# freesoc_mini_1_0.net
KiCad netlist of a schematic drawn in EAGLE
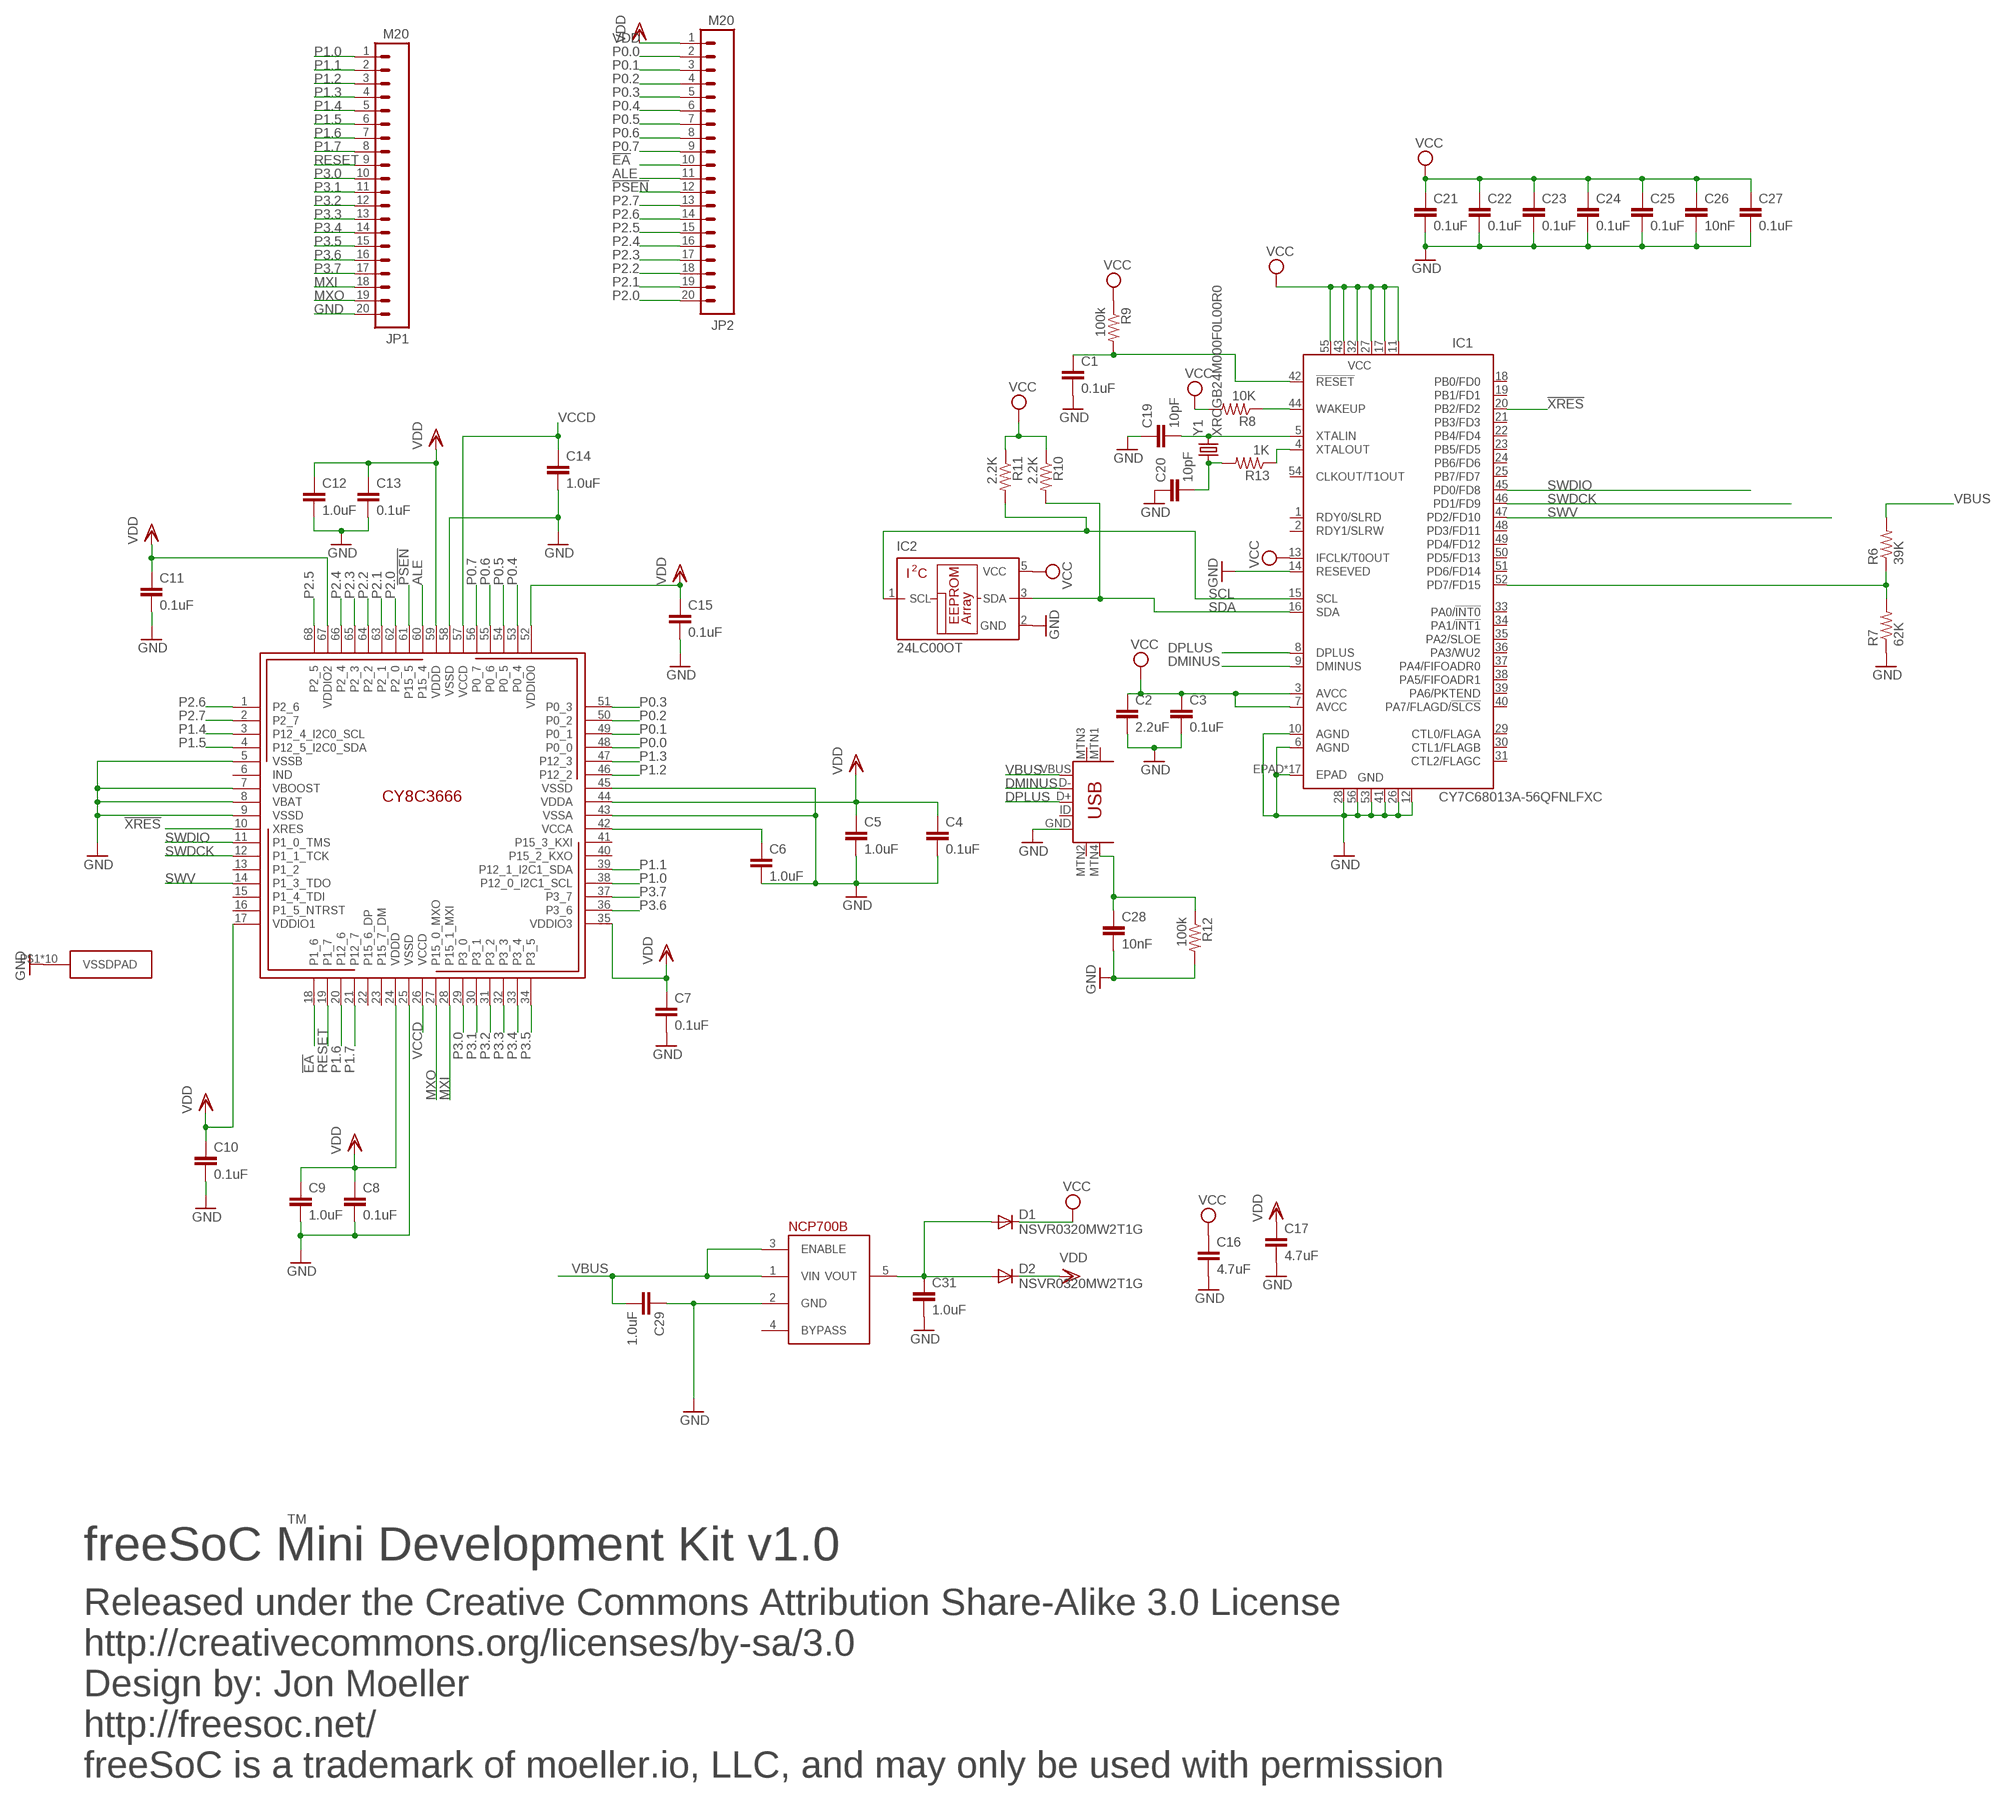
[diagram p0: schematic, sheet 1]

(export (version "E")
  (design (tool "Eeschema 10.0.6"))
  (components
    (comp (ref "C1")
      (value "0.1uF")
      (footprint "eagle-import:0402-CAP")
      (libsource (lib "eagle-import") (part "CAP0402-CAP"))
    )
    (comp (ref "C2")
      (value "2.2uF")
      (footprint "eagle-import:0402-CAP")
      (libsource (lib "eagle-import") (part "CAP0402-CAP"))
    )
    (comp (ref "C3")
      (value "0.1uF")
      (footprint "eagle-import:0402-CAP")
      (libsource (lib "eagle-import") (part "CAP0402-CAP"))
    )
    (comp (ref "C4")
      (value "0.1uF")
      (footprint "eagle-import:0402-CAP")
      (libsource (lib "eagle-import") (part "CAP0402-CAP"))
    )
    (comp (ref "C5")
      (value "1.0uF")
      (footprint "eagle-import:0402-CAP")
      (libsource (lib "eagle-import") (part "CAP0402-CAP"))
    )
    (comp (ref "C6")
      (value "1.0uF")
      (footprint "eagle-import:0402-CAP")
      (libsource (lib "eagle-import") (part "CAP0402-CAP"))
    )
    (comp (ref "C7")
      (value "0.1uF")
      (footprint "eagle-import:0402-CAP")
      (libsource (lib "eagle-import") (part "CAP0402-CAP"))
    )
    (comp (ref "C8")
      (value "0.1uF")
      (footprint "eagle-import:0402-CAP")
      (libsource (lib "eagle-import") (part "CAP0402-CAP"))
    )
    (comp (ref "C9")
      (value "1.0uF")
      (footprint "eagle-import:0402-CAP")
      (libsource (lib "eagle-import") (part "CAP0402-CAP"))
    )
    (comp (ref "C10")
      (value "0.1uF")
      (footprint "eagle-import:0402-CAP")
      (libsource (lib "eagle-import") (part "CAP0402-CAP"))
    )
    (comp (ref "C11")
      (value "0.1uF")
      (footprint "eagle-import:0402-CAP")
      (libsource (lib "eagle-import") (part "CAP0402-CAP"))
    )
    (comp (ref "C12")
      (value "1.0uF")
      (footprint "eagle-import:0402-CAP")
      (libsource (lib "eagle-import") (part "CAP0402-CAP"))
    )
    (comp (ref "C13")
      (value "0.1uF")
      (footprint "eagle-import:0402-CAP")
      (libsource (lib "eagle-import") (part "CAP0402-CAP"))
    )
    (comp (ref "C14")
      (value "1.0uF")
      (footprint "eagle-import:0402-CAP")
      (libsource (lib "eagle-import") (part "CAP0402-CAP"))
    )
    (comp (ref "C15")
      (value "0.1uF")
      (footprint "eagle-import:0402-CAP")
      (libsource (lib "eagle-import") (part "CAP0402-CAP"))
    )
    (comp (ref "C16")
      (value "4.7uF")
      (footprint "eagle-import:0603-CAP")
      (libsource (lib "eagle-import") (part "CAP0603-CAP"))
    )
    (comp (ref "C17")
      (value "4.7uF")
      (footprint "eagle-import:0603-CAP")
      (libsource (lib "eagle-import") (part "CAP0603-CAP"))
    )
    (comp (ref "C19")
      (value "10pF")
      (footprint "eagle-import:0402-CAP")
      (libsource (lib "eagle-import") (part "CAP0402-CAP"))
    )
    (comp (ref "C20")
      (value "10pF")
      (footprint "eagle-import:0402-CAP")
      (libsource (lib "eagle-import") (part "CAP0402-CAP"))
    )
    (comp (ref "C21")
      (value "0.1uF")
      (footprint "eagle-import:0402-CAP")
      (libsource (lib "eagle-import") (part "CAP0402-CAP"))
    )
    (comp (ref "C22")
      (value "0.1uF")
      (footprint "eagle-import:0402-CAP")
      (libsource (lib "eagle-import") (part "CAP0402-CAP"))
    )
    (comp (ref "C23")
      (value "0.1uF")
      (footprint "eagle-import:0402-CAP")
      (libsource (lib "eagle-import") (part "CAP0402-CAP"))
    )
    (comp (ref "C24")
      (value "0.1uF")
      (footprint "eagle-import:0402-CAP")
      (libsource (lib "eagle-import") (part "CAP0402-CAP"))
    )
    (comp (ref "C25")
      (value "0.1uF")
      (footprint "eagle-import:0402-CAP")
      (libsource (lib "eagle-import") (part "CAP0402-CAP"))
    )
    (comp (ref "C26")
      (value "10nF")
      (footprint "eagle-import:0402-CAP")
      (libsource (lib "eagle-import") (part "CAP0402-CAP"))
    )
    (comp (ref "C27")
      (value "0.1uF")
      (footprint "eagle-import:0402-CAP")
      (libsource (lib "eagle-import") (part "CAP0402-CAP"))
    )
    (comp (ref "C28")
      (value "10nF")
      (footprint "eagle-import:0402-CAP")
      (libsource (lib "eagle-import") (part "CAP0402-CAP"))
    )
    (comp (ref "C29")
      (value "1.0uF")
      (footprint "eagle-import:0402-CAP")
      (libsource (lib "eagle-import") (part "CAP0402-CAP"))
    )
    (comp (ref "C31")
      (value "1.0uF")
      (footprint "eagle-import:0402-CAP")
      (libsource (lib "eagle-import") (part "CAP0402-CAP"))
    )
    (comp (ref "D1")
      (value "NSVR0320MW2T1G")
      (footprint "eagle-import:SOD-323")
      (libsource (lib "eagle-import") (part "DIODESOD"))
    )
    (comp (ref "D2")
      (value "NSVR0320MW2T1G")
      (footprint "eagle-import:SOD-323")
      (libsource (lib "eagle-import") (part "DIODESOD"))
    )
    (comp (ref "IC1")
      (value "CY7C68013A-56QFNLFXC")
      (footprint "eagle-import:QFN56")
      (libsource (lib "eagle-import") (part "CY7C6801A-56QFNLFXC3"))
    )
    (comp (ref "IC2")
      (value "24LC00OT")
      (footprint "eagle-import:SOT23-5L")
      (libsource (lib "eagle-import") (part "2400OTLC"))
    )
    (comp (ref "JP1")
      (value "M20")
      (footprint "eagle-import:1X20")
      (libsource (lib "eagle-import") (part "M20"))
    )
    (comp (ref "JP2")
      (value "M20")
      (footprint "eagle-import:1X20")
      (libsource (lib "eagle-import") (part "M20"))
    )
    (comp (ref "R6")
      (value "39K")
      (footprint "eagle-import:0402-RES")
      (libsource (lib "eagle-import") (part "RESISTOR0402-RES"))
    )
    (comp (ref "R7")
      (value "62K")
      (footprint "eagle-import:0402-RES")
      (libsource (lib "eagle-import") (part "RESISTOR0402-RES"))
    )
    (comp (ref "R8")
      (value "10K")
      (footprint "eagle-import:0402-RES")
      (libsource (lib "eagle-import") (part "RESISTOR0402-RES"))
    )
    (comp (ref "R9")
      (value "100k")
      (footprint "eagle-import:0402-RES")
      (libsource (lib "eagle-import") (part "RESISTOR0402-RES"))
    )
    (comp (ref "R10")
      (value "2.2K")
      (footprint "eagle-import:0402-RES")
      (libsource (lib "eagle-import") (part "RESISTOR0402-RES"))
    )
    (comp (ref "R11")
      (value "2.2K")
      (footprint "eagle-import:0402-RES")
      (libsource (lib "eagle-import") (part "RESISTOR0402-RES"))
    )
    (comp (ref "R12")
      (value "100k")
      (footprint "eagle-import:0402-RES")
      (libsource (lib "eagle-import") (part "RESISTOR0402-RES"))
    )
    (comp (ref "R13")
      (value "1K")
      (footprint "eagle-import:0402-RES")
      (libsource (lib "eagle-import") (part "RESISTOR0402-RES"))
    )
    (comp (ref "U$1")
      (value "CY8C3X66LTI")
      (footprint "eagle-import:QFN-68")
      (fields (field (name "PN") "CY8C5568LTI-114"))
      (libsource (lib "eagle-import") (part "CY8C3X66LTI"))
    )
    (comp (ref "U$3")
      (value "FAN2558S36X")
      (footprint "eagle-import:TSOP-5")
      (libsource (lib "eagle-import") (part "NCP700B"))
    )
    (comp (ref "USB-MINIB")
      (value "USB-MINIB-5PIN")
      (footprint "eagle-import:USB-MINIB")
      (libsource (lib "eagle-import") (part "USB-MINIB-5PIN"))
    )
    (comp (ref "Y1")
      (value "XRCGB24M000F0L00R0")
      (footprint "eagle-import:CRYSTAL_RESONATOR")
      (libsource (lib "eagle-import") (part "CRYSTALXRCGB"))
    )
  )
  (nets
    (net (code "1") (name "/ALE") (class "Default")
      (node (ref "JP2") (pin "11") (pinfunction "11_11") (pintype "passive"))
      (node (ref "U$1") (pin "60") (pinfunction "P15_4_60") (pintype "passive"))
    )
    (net (code "2") (name "/DMINUS") (class "Default")
      (node (ref "IC1") (pin "9") (pinfunction "DMINUS_9") (pintype "bidirectional"))
      (node (ref "USB-MINIB") (pin "D-") (pinfunction "D-_D-") (pintype "bidirectional"))
    )
    (net (code "3") (name "/DPLUS") (class "Default")
      (node (ref "IC1") (pin "8") (pinfunction "DPLUS_8") (pintype "bidirectional"))
      (node (ref "USB-MINIB") (pin "D+") (pinfunction "D+_D+") (pintype "bidirectional"))
    )
    (net (code "4") (name "/MXI") (class "Default")
      (node (ref "JP1") (pin "18") (pinfunction "18_18") (pintype "passive"))
      (node (ref "U$1") (pin "28") (pinfunction "P15_1_MXI_28") (pintype "passive"))
    )
    (net (code "5") (name "/MXO") (class "Default")
      (node (ref "JP1") (pin "19") (pinfunction "19_19") (pintype "passive"))
      (node (ref "U$1") (pin "27") (pinfunction "P15_0_MXO_27") (pintype "passive"))
    )
    (net (code "6") (name "/P0.0") (class "Default")
      (node (ref "JP2") (pin "2") (pinfunction "2_2") (pintype "passive"))
      (node (ref "U$1") (pin "48") (pinfunction "P0_0_48") (pintype "passive"))
    )
    (net (code "7") (name "/P0.1") (class "Default")
      (node (ref "JP2") (pin "3") (pinfunction "3_3") (pintype "passive"))
      (node (ref "U$1") (pin "49") (pinfunction "P0_1_49") (pintype "passive"))
    )
    (net (code "8") (name "/P0.2") (class "Default")
      (node (ref "JP2") (pin "4") (pinfunction "4_4") (pintype "passive"))
      (node (ref "U$1") (pin "50") (pinfunction "P0_2_50") (pintype "passive"))
    )
    (net (code "9") (name "/P0.3") (class "Default")
      (node (ref "JP2") (pin "5") (pinfunction "5_5") (pintype "passive"))
      (node (ref "U$1") (pin "51") (pinfunction "P0_3_51") (pintype "passive"))
    )
    (net (code "10") (name "/P0.4") (class "Default")
      (node (ref "JP2") (pin "6") (pinfunction "6_6") (pintype "passive"))
      (node (ref "U$1") (pin "53") (pinfunction "P0_4_53") (pintype "passive"))
    )
    (net (code "11") (name "/P0.5") (class "Default")
      (node (ref "JP2") (pin "7") (pinfunction "7_7") (pintype "passive"))
      (node (ref "U$1") (pin "54") (pinfunction "P0_5_54") (pintype "passive"))
    )
    (net (code "12") (name "/P0.6") (class "Default")
      (node (ref "JP2") (pin "8") (pinfunction "8_8") (pintype "passive"))
      (node (ref "U$1") (pin "55") (pinfunction "P0_6_55") (pintype "passive"))
    )
    (net (code "13") (name "/P0.7") (class "Default")
      (node (ref "JP2") (pin "9") (pinfunction "9_9") (pintype "passive"))
      (node (ref "U$1") (pin "56") (pinfunction "P0_7_56") (pintype "passive"))
    )
    (net (code "14") (name "/P1.0") (class "Default")
      (node (ref "JP1") (pin "1") (pinfunction "1_1") (pintype "passive"))
      (node (ref "U$1") (pin "38") (pinfunction "P12_0_I2C1_SCL_38") (pintype "passive"))
    )
    (net (code "15") (name "/P1.1") (class "Default")
      (node (ref "JP1") (pin "2") (pinfunction "2_2") (pintype "passive"))
      (node (ref "U$1") (pin "39") (pinfunction "P12_1_I2C1_SDA_39") (pintype "passive"))
    )
    (net (code "16") (name "/P1.2") (class "Default")
      (node (ref "JP1") (pin "3") (pinfunction "3_3") (pintype "passive"))
      (node (ref "U$1") (pin "46") (pinfunction "P12_2_46") (pintype "passive"))
    )
    (net (code "17") (name "/P1.3") (class "Default")
      (node (ref "JP1") (pin "4") (pinfunction "4_4") (pintype "passive"))
      (node (ref "U$1") (pin "47") (pinfunction "P12_3_47") (pintype "passive"))
    )
    (net (code "18") (name "/P1.4") (class "Default")
      (node (ref "JP1") (pin "5") (pinfunction "5_5") (pintype "passive"))
      (node (ref "U$1") (pin "3") (pinfunction "P12_4_I2C0_SCL_3") (pintype "passive"))
    )
    (net (code "19") (name "/P1.5") (class "Default")
      (node (ref "JP1") (pin "6") (pinfunction "6_6") (pintype "passive"))
      (node (ref "U$1") (pin "4") (pinfunction "P12_5_I2C0_SDA_4") (pintype "passive"))
    )
    (net (code "20") (name "/P1.6") (class "Default")
      (node (ref "JP1") (pin "7") (pinfunction "7_7") (pintype "passive"))
      (node (ref "U$1") (pin "20") (pinfunction "P12_6_20") (pintype "passive"))
    )
    (net (code "21") (name "/P1.7") (class "Default")
      (node (ref "JP1") (pin "8") (pinfunction "8_8") (pintype "passive"))
      (node (ref "U$1") (pin "21") (pinfunction "P12_7_21") (pintype "passive"))
    )
    (net (code "22") (name "/P2.0") (class "Default")
      (node (ref "JP2") (pin "20") (pinfunction "20_20") (pintype "passive"))
      (node (ref "U$1") (pin "62") (pinfunction "P2_0_62") (pintype "passive"))
    )
    (net (code "23") (name "/P2.1") (class "Default")
      (node (ref "JP2") (pin "19") (pinfunction "19_19") (pintype "passive"))
      (node (ref "U$1") (pin "63") (pinfunction "P2_1_63") (pintype "passive"))
    )
    (net (code "24") (name "/P2.2") (class "Default")
      (node (ref "JP2") (pin "18") (pinfunction "18_18") (pintype "passive"))
      (node (ref "U$1") (pin "64") (pinfunction "P2_2_64") (pintype "passive"))
    )
    (net (code "25") (name "/P2.3") (class "Default")
      (node (ref "JP2") (pin "17") (pinfunction "17_17") (pintype "passive"))
      (node (ref "U$1") (pin "65") (pinfunction "P2_3_65") (pintype "passive"))
    )
    (net (code "26") (name "/P2.4") (class "Default")
      (node (ref "JP2") (pin "16") (pinfunction "16_16") (pintype "passive"))
      (node (ref "U$1") (pin "66") (pinfunction "P2_4_66") (pintype "passive"))
    )
    (net (code "27") (name "/P2.5") (class "Default")
      (node (ref "JP2") (pin "15") (pinfunction "15_15") (pintype "passive"))
      (node (ref "U$1") (pin "68") (pinfunction "P2_5_68") (pintype "passive"))
    )
    (net (code "28") (name "/P2.6") (class "Default")
      (node (ref "JP2") (pin "14") (pinfunction "14_14") (pintype "passive"))
      (node (ref "U$1") (pin "1") (pinfunction "P2_6_1") (pintype "passive"))
    )
    (net (code "29") (name "/P2.7") (class "Default")
      (node (ref "JP2") (pin "13") (pinfunction "13_13") (pintype "passive"))
      (node (ref "U$1") (pin "2") (pinfunction "P2_7_2") (pintype "passive"))
    )
    (net (code "30") (name "/P3.0") (class "Default")
      (node (ref "JP1") (pin "10") (pinfunction "10_10") (pintype "passive"))
      (node (ref "U$1") (pin "29") (pinfunction "P3_0_29") (pintype "passive"))
    )
    (net (code "31") (name "/P3.1") (class "Default")
      (node (ref "JP1") (pin "11") (pinfunction "11_11") (pintype "passive"))
      (node (ref "U$1") (pin "30") (pinfunction "P3_1_30") (pintype "passive"))
    )
    (net (code "32") (name "/P3.2") (class "Default")
      (node (ref "JP1") (pin "12") (pinfunction "12_12") (pintype "passive"))
      (node (ref "U$1") (pin "31") (pinfunction "P3_2_31") (pintype "passive"))
    )
    (net (code "33") (name "/P3.3") (class "Default")
      (node (ref "JP1") (pin "13") (pinfunction "13_13") (pintype "passive"))
      (node (ref "U$1") (pin "32") (pinfunction "P3_3_32") (pintype "passive"))
    )
    (net (code "34") (name "/P3.4") (class "Default")
      (node (ref "JP1") (pin "14") (pinfunction "14_14") (pintype "passive"))
      (node (ref "U$1") (pin "33") (pinfunction "P3_4_33") (pintype "passive"))
    )
    (net (code "35") (name "/P3.5") (class "Default")
      (node (ref "JP1") (pin "15") (pinfunction "15_15") (pintype "passive"))
      (node (ref "U$1") (pin "34") (pinfunction "P3_5_34") (pintype "passive"))
    )
    (net (code "36") (name "/P3.6") (class "Default")
      (node (ref "JP1") (pin "16") (pinfunction "16_16") (pintype "passive"))
      (node (ref "U$1") (pin "36") (pinfunction "P3_6_36") (pintype "passive"))
    )
    (net (code "37") (name "/P3.7") (class "Default")
      (node (ref "JP1") (pin "17") (pinfunction "17_17") (pintype "passive"))
      (node (ref "U$1") (pin "37") (pinfunction "P3_7_37") (pintype "passive"))
    )
    (net (code "38") (name "/RESET") (class "Default")
      (node (ref "JP1") (pin "9") (pinfunction "9_9") (pintype "passive"))
      (node (ref "U$1") (pin "19") (pinfunction "P1_7_19") (pintype "passive"))
    )
    (net (code "39") (name "/SCL") (class "Default")
      (node (ref "IC1") (pin "15") (pinfunction "SCL_15") (pintype "output"))
      (node (ref "IC2") (pin "1") (pinfunction "SCL_1") (pintype "input"))
      (node (ref "R11") (pin "2") (pinfunction "2_2") (pintype "passive"))
    )
    (net (code "40") (name "/SDA") (class "Default")
      (node (ref "IC1") (pin "16") (pinfunction "SDA_16") (pintype "bidirectional"))
      (node (ref "IC2") (pin "3") (pinfunction "SDA_3") (pintype "bidirectional"))
      (node (ref "R10") (pin "2") (pinfunction "2_2") (pintype "passive"))
    )
    (net (code "41") (name "/SWDCK") (class "Default")
      (node (ref "IC1") (pin "46") (pinfunction "PD1/FD9_46") (pintype "bidirectional"))
      (node (ref "U$1") (pin "12") (pinfunction "P1_1_TCK_12") (pintype "passive"))
    )
    (net (code "42") (name "/SWDIO") (class "Default")
      (node (ref "IC1") (pin "45") (pinfunction "PD0/FD8_45") (pintype "bidirectional"))
      (node (ref "U$1") (pin "11") (pinfunction "P1_0_TMS_11") (pintype "passive"))
    )
    (net (code "43") (name "/SWV") (class "Default")
      (node (ref "IC1") (pin "47") (pinfunction "PD2/FD10_47") (pintype "bidirectional"))
      (node (ref "U$1") (pin "14") (pinfunction "P1_3_TDO_14") (pintype "passive"))
    )
    (net (code "44") (name "/VBUS") (class "Default")
      (node (ref "C29") (pin "2") (pinfunction "2_2") (pintype "passive"))
      (node (ref "R6") (pin "2") (pinfunction "2_2") (pintype "passive"))
      (node (ref "U$3") (pin "1") (pinfunction "VIN_1") (pintype "bidirectional"))
      (node (ref "U$3") (pin "3") (pinfunction "ENABLE_3") (pintype "bidirectional"))
      (node (ref "USB-MINIB") (pin "VBUS") (pinfunction "VBUS_VBUS") (pintype "bidirectional"))
    )
    (net (code "45") (name "/VCCD") (class "Default")
      (node (ref "C14") (pin "1") (pinfunction "1_1") (pintype "passive"))
      (node (ref "U$1") (pin "26") (pinfunction "VCCD_26") (pintype "passive"))
      (node (ref "U$1") (pin "57") (pinfunction "VCCD_57") (pintype "passive"))
    )
    (net (code "46") (name "/~{EA}") (class "Default")
      (node (ref "JP2") (pin "10") (pinfunction "10_10") (pintype "passive"))
      (node (ref "U$1") (pin "18") (pinfunction "P1_6_18") (pintype "passive"))
    )
    (net (code "47") (name "/~{PSEN}") (class "Default")
      (node (ref "JP2") (pin "12") (pinfunction "12_12") (pintype "passive"))
      (node (ref "U$1") (pin "61") (pinfunction "P15_5_61") (pintype "passive"))
    )
    (net (code "48") (name "/~{XRES}") (class "Default")
      (node (ref "IC1") (pin "20") (pinfunction "PB2/FD2_20") (pintype "bidirectional"))
      (node (ref "U$1") (pin "10") (pinfunction "XRES_10") (pintype "passive"))
    )
    (net (code "49") (name "GND") (class "Default")
      (node (ref "C1") (pin "2") (pinfunction "2_2") (pintype "passive"))
      (node (ref "C10") (pin "2") (pinfunction "2_2") (pintype "passive"))
      (node (ref "C11") (pin "2") (pinfunction "2_2") (pintype "passive"))
      (node (ref "C12") (pin "2") (pinfunction "2_2") (pintype "passive"))
      (node (ref "C13") (pin "2") (pinfunction "2_2") (pintype "passive"))
      (node (ref "C14") (pin "2") (pinfunction "2_2") (pintype "passive"))
      (node (ref "C15") (pin "2") (pinfunction "2_2") (pintype "passive"))
      (node (ref "C16") (pin "2") (pinfunction "2_2") (pintype "passive"))
      (node (ref "C17") (pin "2") (pinfunction "2_2") (pintype "passive"))
      (node (ref "C19") (pin "1") (pinfunction "1_1") (pintype "passive"))
      (node (ref "C2") (pin "2") (pinfunction "2_2") (pintype "passive"))
      (node (ref "C20") (pin "1") (pinfunction "1_1") (pintype "passive"))
      (node (ref "C21") (pin "2") (pinfunction "2_2") (pintype "passive"))
      (node (ref "C22") (pin "2") (pinfunction "2_2") (pintype "passive"))
      (node (ref "C23") (pin "2") (pinfunction "2_2") (pintype "passive"))
      (node (ref "C24") (pin "2") (pinfunction "2_2") (pintype "passive"))
      (node (ref "C25") (pin "2") (pinfunction "2_2") (pintype "passive"))
      (node (ref "C26") (pin "2") (pinfunction "2_2") (pintype "passive"))
      (node (ref "C27") (pin "2") (pinfunction "2_2") (pintype "passive"))
      (node (ref "C28") (pin "2") (pinfunction "2_2") (pintype "passive"))
      (node (ref "C29") (pin "1") (pinfunction "1_1") (pintype "passive"))
      (node (ref "C3") (pin "2") (pinfunction "2_2") (pintype "passive"))
      (node (ref "C31") (pin "2") (pinfunction "2_2") (pintype "passive"))
      (node (ref "C4") (pin "2") (pinfunction "2_2") (pintype "passive"))
      (node (ref "C5") (pin "2") (pinfunction "2_2") (pintype "passive"))
      (node (ref "C6") (pin "2") (pinfunction "2_2") (pintype "passive"))
      (node (ref "C7") (pin "2") (pinfunction "2_2") (pintype "passive"))
      (node (ref "C8") (pin "2") (pinfunction "2_2") (pintype "passive"))
      (node (ref "C9") (pin "2") (pinfunction "2_2") (pintype "passive"))
      (node (ref "IC1") (pin "10") (pinfunction "AGND_10") (pintype "input"))
      (node (ref "IC1") (pin "12") (pinfunction "GND_12") (pintype "input"))
      (node (ref "IC1") (pin "14") (pinfunction "RESEVED_14") (pintype "input"))
      (node (ref "IC1") (pin "26") (pinfunction "GND_26") (pintype "input"))
      (node (ref "IC1") (pin "28") (pinfunction "GND_28") (pintype "input"))
      (node (ref "IC1") (pin "41") (pinfunction "GND_41") (pintype "input"))
      (node (ref "IC1") (pin "53") (pinfunction "GND_53") (pintype "input"))
      (node (ref "IC1") (pin "56") (pinfunction "GND_56") (pintype "input"))
      (node (ref "IC1") (pin "6") (pinfunction "AGND_6") (pintype "input"))
      (node (ref "IC1") (pin "EPAD") (pinfunction "EPAD_EPAD") (pintype "passive"))
      (node (ref "IC1") (pin "P$1") (pinfunction "EPAD_P$1") (pintype "passive"))
      (node (ref "IC1") (pin "P$10") (pinfunction "EPAD_P$10") (pintype "passive"))
      (node (ref "IC1") (pin "P$11") (pinfunction "EPAD_P$11") (pintype "passive"))
      (node (ref "IC1") (pin "P$12") (pinfunction "EPAD_P$12") (pintype "passive"))
      (node (ref "IC1") (pin "P$13") (pinfunction "EPAD_P$13") (pintype "passive"))
      (node (ref "IC1") (pin "P$14") (pinfunction "EPAD_P$14") (pintype "passive"))
      (node (ref "IC1") (pin "P$15") (pinfunction "EPAD_P$15") (pintype "passive"))
      (node (ref "IC1") (pin "P$16") (pinfunction "EPAD_P$16") (pintype "passive"))
      (node (ref "IC1") (pin "P$2") (pinfunction "EPAD_P$2") (pintype "passive"))
      (node (ref "IC1") (pin "P$3") (pinfunction "EPAD_P$3") (pintype "passive"))
      (node (ref "IC1") (pin "P$4") (pinfunction "EPAD_P$4") (pintype "passive"))
      (node (ref "IC1") (pin "P$5") (pinfunction "EPAD_P$5") (pintype "passive"))
      (node (ref "IC1") (pin "P$6") (pinfunction "EPAD_P$6") (pintype "passive"))
      (node (ref "IC1") (pin "P$7") (pinfunction "EPAD_P$7") (pintype "passive"))
      (node (ref "IC1") (pin "P$8") (pinfunction "EPAD_P$8") (pintype "passive"))
      (node (ref "IC1") (pin "P$9") (pinfunction "EPAD_P$9") (pintype "passive"))
      (node (ref "IC2") (pin "2") (pinfunction "GND_2") (pintype "power_in"))
      (node (ref "JP1") (pin "20") (pinfunction "20_20") (pintype "passive"))
      (node (ref "R12") (pin "2") (pinfunction "2_2") (pintype "passive"))
      (node (ref "R7") (pin "1") (pinfunction "1_1") (pintype "passive"))
      (node (ref "U$1") (pin "25") (pinfunction "VSSD_25") (pintype "passive"))
      (node (ref "U$1") (pin "43") (pinfunction "VSSA_43") (pintype "passive"))
      (node (ref "U$1") (pin "45") (pinfunction "VSSD_45") (pintype "passive"))
      (node (ref "U$1") (pin "5") (pinfunction "VSSB_5") (pintype "passive"))
      (node (ref "U$1") (pin "58") (pinfunction "VSSD_58") (pintype "passive"))
      (node (ref "U$1") (pin "7") (pinfunction "VBOOST_7") (pintype "passive"))
      (node (ref "U$1") (pin "8") (pinfunction "VBAT_8") (pintype "passive"))
      (node (ref "U$1") (pin "9") (pinfunction "VSSD_9") (pintype "passive"))
      (node (ref "U$1") (pin "P$1") (pinfunction "VSSDPAD_P$1") (pintype "power_in"))
      (node (ref "U$1") (pin "P$2") (pinfunction "VSSDPAD_P$2") (pintype "power_in"))
      (node (ref "U$1") (pin "P$3") (pinfunction "VSSDPAD_P$3") (pintype "power_in"))
      (node (ref "U$1") (pin "P$4") (pinfunction "VSSDPAD_P$4") (pintype "power_in"))
      (node (ref "U$1") (pin "P$5") (pinfunction "VSSDPAD_P$5") (pintype "power_in"))
      (node (ref "U$1") (pin "P$6") (pinfunction "VSSDPAD_P$6") (pintype "power_in"))
      (node (ref "U$1") (pin "P$7") (pinfunction "VSSDPAD_P$7") (pintype "power_in"))
      (node (ref "U$1") (pin "P$8") (pinfunction "VSSDPAD_P$8") (pintype "power_in"))
      (node (ref "U$1") (pin "P$9") (pinfunction "VSSDPAD_P$9") (pintype "power_in"))
      (node (ref "U$1") (pin "PAD") (pinfunction "VSSDPAD_PAD") (pintype "power_in"))
      (node (ref "U$3") (pin "2") (pinfunction "GND_2") (pintype "bidirectional"))
      (node (ref "USB-MINIB") (pin "GND") (pinfunction "GND_GND") (pintype "bidirectional"))
    )
    (net (code "50") (name "Net-(C28-Pad1)") (class "Default")
      (node (ref "C28") (pin "1") (pinfunction "1_1") (pintype "passive"))
      (node (ref "R12") (pin "1") (pinfunction "1_1") (pintype "passive"))
      (node (ref "USB-MINIB") (pin "MTN4") (pinfunction "MTN4_MTN4") (pintype "bidirectional"))
    )
    (net (code "51") (name "Net-(D1-A)") (class "Default")
      (node (ref "C31") (pin "1") (pinfunction "1_1") (pintype "passive"))
      (node (ref "D1") (pin "2") (pinfunction "A_2") (pintype "passive"))
      (node (ref "D2") (pin "2") (pinfunction "A_2") (pintype "passive"))
      (node (ref "U$3") (pin "5") (pinfunction "VOUT_5") (pintype "bidirectional"))
    )
    (net (code "52") (name "Net-(IC1-PD7{slash}FD15)") (class "Default")
      (node (ref "IC1") (pin "52") (pinfunction "PD7/FD15_52") (pintype "bidirectional"))
      (node (ref "R6") (pin "1") (pinfunction "1_1") (pintype "passive"))
      (node (ref "R7") (pin "2") (pinfunction "2_2") (pintype "passive"))
    )
    (net (code "53") (name "Net-(IC1-WAKEUP)") (class "Default")
      (node (ref "IC1") (pin "44") (pinfunction "WAKEUP_44") (pintype "input"))
      (node (ref "R8") (pin "1") (pinfunction "1_1") (pintype "passive"))
    )
    (net (code "54") (name "Net-(IC1-XTALIN)") (class "Default")
      (node (ref "C19") (pin "2") (pinfunction "2_2") (pintype "passive"))
      (node (ref "IC1") (pin "5") (pinfunction "XTALIN_5") (pintype "input"))
      (node (ref "Y1") (pin "P$4") (pinfunction "2_P$4") (pintype "passive"))
    )
    (net (code "55") (name "Net-(IC1-XTALOUT)") (class "Default")
      (node (ref "IC1") (pin "4") (pinfunction "XTALOUT_4") (pintype "input"))
      (node (ref "R13") (pin "1") (pinfunction "1_1") (pintype "passive"))
    )
    (net (code "56") (name "Net-(IC1-~{RESET})") (class "Default")
      (node (ref "C1") (pin "1") (pinfunction "1_1") (pintype "passive"))
      (node (ref "IC1") (pin "42") (pinfunction "~{RESET}_42") (pintype "input"))
      (node (ref "R9") (pin "2") (pinfunction "2_2") (pintype "passive"))
    )
    (net (code "57") (name "Net-(U$1A-VCCA)") (class "Default")
      (node (ref "C6") (pin "1") (pinfunction "1_1") (pintype "passive"))
      (node (ref "U$1") (pin "42") (pinfunction "VCCA_42") (pintype "passive"))
    )
    (net (code "58") (name "Net-(Y1-1)") (class "Default")
      (node (ref "C20") (pin "2") (pinfunction "2_2") (pintype "passive"))
      (node (ref "R13") (pin "2") (pinfunction "2_2") (pintype "passive"))
      (node (ref "Y1") (pin "P$1") (pinfunction "1_P$1") (pintype "passive"))
    )
    (net (code "59") (name "VCC") (class "Default")
      (node (ref "C16") (pin "1") (pinfunction "1_1") (pintype "passive"))
      (node (ref "C2") (pin "1") (pinfunction "1_1") (pintype "passive"))
      (node (ref "C21") (pin "1") (pinfunction "1_1") (pintype "passive"))
      (node (ref "C22") (pin "1") (pinfunction "1_1") (pintype "passive"))
      (node (ref "C23") (pin "1") (pinfunction "1_1") (pintype "passive"))
      (node (ref "C24") (pin "1") (pinfunction "1_1") (pintype "passive"))
      (node (ref "C25") (pin "1") (pinfunction "1_1") (pintype "passive"))
      (node (ref "C26") (pin "1") (pinfunction "1_1") (pintype "passive"))
      (node (ref "C27") (pin "1") (pinfunction "1_1") (pintype "passive"))
      (node (ref "C3") (pin "1") (pinfunction "1_1") (pintype "passive"))
      (node (ref "D1") (pin "1") (pinfunction "C_1") (pintype "passive"))
      (node (ref "IC1") (pin "11") (pinfunction "VCC_11") (pintype "input"))
      (node (ref "IC1") (pin "13") (pinfunction "IFCLK/T0OUT_13") (pintype "bidirectional"))
      (node (ref "IC1") (pin "17") (pinfunction "VCC_17") (pintype "input"))
      (node (ref "IC1") (pin "27") (pinfunction "VCC_27") (pintype "input"))
      (node (ref "IC1") (pin "3") (pinfunction "AVCC_3") (pintype "input"))
      (node (ref "IC1") (pin "32") (pinfunction "VCC_32") (pintype "input"))
      (node (ref "IC1") (pin "43") (pinfunction "VCC_43") (pintype "input"))
      (node (ref "IC1") (pin "55") (pinfunction "VCC_55") (pintype "input"))
      (node (ref "IC1") (pin "7") (pinfunction "AVCC_7") (pintype "input"))
      (node (ref "IC2") (pin "5") (pinfunction "VCC_5") (pintype "power_in"))
      (node (ref "R10") (pin "1") (pinfunction "1_1") (pintype "passive"))
      (node (ref "R11") (pin "1") (pinfunction "1_1") (pintype "passive"))
      (node (ref "R8") (pin "2") (pinfunction "2_2") (pintype "passive"))
      (node (ref "R9") (pin "1") (pinfunction "1_1") (pintype "passive"))
    )
    (net (code "60") (name "VDD") (class "Default")
      (node (ref "C10") (pin "1") (pinfunction "1_1") (pintype "passive"))
      (node (ref "C11") (pin "1") (pinfunction "1_1") (pintype "passive"))
      (node (ref "C12") (pin "1") (pinfunction "1_1") (pintype "passive"))
      (node (ref "C13") (pin "1") (pinfunction "1_1") (pintype "passive"))
      (node (ref "C15") (pin "1") (pinfunction "1_1") (pintype "passive"))
      (node (ref "C17") (pin "1") (pinfunction "1_1") (pintype "passive"))
      (node (ref "C4") (pin "1") (pinfunction "1_1") (pintype "passive"))
      (node (ref "C5") (pin "1") (pinfunction "1_1") (pintype "passive"))
      (node (ref "C7") (pin "1") (pinfunction "1_1") (pintype "passive"))
      (node (ref "C8") (pin "1") (pinfunction "1_1") (pintype "passive"))
      (node (ref "C9") (pin "1") (pinfunction "1_1") (pintype "passive"))
      (node (ref "D2") (pin "1") (pinfunction "C_1") (pintype "passive"))
      (node (ref "JP2") (pin "1") (pinfunction "1_1") (pintype "passive"))
      (node (ref "U$1") (pin "17") (pinfunction "VDDIO1_17") (pintype "passive"))
      (node (ref "U$1") (pin "24") (pinfunction "VDDD_24") (pintype "passive"))
      (node (ref "U$1") (pin "35") (pinfunction "VDDIO3_35") (pintype "passive"))
      (node (ref "U$1") (pin "44") (pinfunction "VDDA_44") (pintype "passive"))
      (node (ref "U$1") (pin "52") (pinfunction "VDDIO0_52") (pintype "passive"))
      (node (ref "U$1") (pin "59") (pinfunction "VDDD_59") (pintype "passive"))
      (node (ref "U$1") (pin "67") (pinfunction "VDDIO2_67") (pintype "passive"))
    )
    (net (code "61") (name "unconnected-(IC1-CLKOUT{slash}T1OUT-Pad54)") (class "Default")
      (node (ref "IC1") (pin "54") (pinfunction "CLKOUT/T1OUT_54") (pintype "input"))
    )
    (net (code "62") (name "unconnected-(IC1-CTL0{slash}FLAGA-Pad29)") (class "Default")
      (node (ref "IC1") (pin "29") (pinfunction "CTL0/FLAGA_29") (pintype "output"))
    )
    (net (code "63") (name "unconnected-(IC1-CTL1{slash}FLAGB-Pad30)") (class "Default")
      (node (ref "IC1") (pin "30") (pinfunction "CTL1/FLAGB_30") (pintype "output"))
    )
    (net (code "64") (name "unconnected-(IC1-CTL2{slash}FLAGC-Pad31)") (class "Default")
      (node (ref "IC1") (pin "31") (pinfunction "CTL2/FLAGC_31") (pintype "output"))
    )
    (net (code "65") (name "unconnected-(IC1-PA0{slash}~{INT0}-Pad33)") (class "Default")
      (node (ref "IC1") (pin "33") (pinfunction "PA0/~{INT0}_33") (pintype "bidirectional"))
    )
    (net (code "66") (name "unconnected-(IC1-PA1{slash}~{INT1}-Pad34)") (class "Default")
      (node (ref "IC1") (pin "34") (pinfunction "PA1/~{INT1}_34") (pintype "bidirectional"))
    )
    (net (code "67") (name "unconnected-(IC1-PA2{slash}SLOE-Pad35)") (class "Default")
      (node (ref "IC1") (pin "35") (pinfunction "PA2/SLOE_35") (pintype "bidirectional"))
    )
    (net (code "68") (name "unconnected-(IC1-PA3{slash}WU2-Pad36)") (class "Default")
      (node (ref "IC1") (pin "36") (pinfunction "PA3/WU2_36") (pintype "bidirectional"))
    )
    (net (code "69") (name "unconnected-(IC1-PA4{slash}FIFOADR0-Pad37)") (class "Default")
      (node (ref "IC1") (pin "37") (pinfunction "PA4/FIFOADR0_37") (pintype "bidirectional"))
    )
    (net (code "70") (name "unconnected-(IC1-PA5{slash}FIFOADR1-Pad38)") (class "Default")
      (node (ref "IC1") (pin "38") (pinfunction "PA5/FIFOADR1_38") (pintype "bidirectional"))
    )
    (net (code "71") (name "unconnected-(IC1-PA6{slash}PKTEND-Pad39)") (class "Default")
      (node (ref "IC1") (pin "39") (pinfunction "PA6/PKTEND_39") (pintype "bidirectional"))
    )
    (net (code "72") (name "unconnected-(IC1-PA7{slash}FLAGD{slash}~{SLCS}-Pad40)") (class "Default")
      (node (ref "IC1") (pin "40") (pinfunction "PA7/FLAGD/~{SLCS}_40") (pintype "bidirectional"))
    )
    (net (code "73") (name "unconnected-(IC1-PB0{slash}FD0-Pad18)") (class "Default")
      (node (ref "IC1") (pin "18") (pinfunction "PB0/FD0_18") (pintype "bidirectional"))
    )
    (net (code "74") (name "unconnected-(IC1-PB1{slash}FD1-Pad19)") (class "Default")
      (node (ref "IC1") (pin "19") (pinfunction "PB1/FD1_19") (pintype "bidirectional"))
    )
    (net (code "75") (name "unconnected-(IC1-PB3{slash}FD3-Pad21)") (class "Default")
      (node (ref "IC1") (pin "21") (pinfunction "PB3/FD3_21") (pintype "bidirectional"))
    )
    (net (code "76") (name "unconnected-(IC1-PB4{slash}FD4-Pad22)") (class "Default")
      (node (ref "IC1") (pin "22") (pinfunction "PB4/FD4_22") (pintype "bidirectional"))
    )
    (net (code "77") (name "unconnected-(IC1-PB5{slash}FD5-Pad23)") (class "Default")
      (node (ref "IC1") (pin "23") (pinfunction "PB5/FD5_23") (pintype "bidirectional"))
    )
    (net (code "78") (name "unconnected-(IC1-PB6{slash}FD6-Pad24)") (class "Default")
      (node (ref "IC1") (pin "24") (pinfunction "PB6/FD6_24") (pintype "bidirectional"))
    )
    (net (code "79") (name "unconnected-(IC1-PB7{slash}FD7-Pad25)") (class "Default")
      (node (ref "IC1") (pin "25") (pinfunction "PB7/FD7_25") (pintype "bidirectional"))
    )
    (net (code "80") (name "unconnected-(IC1-PD3{slash}FD11-Pad48)") (class "Default")
      (node (ref "IC1") (pin "48") (pinfunction "PD3/FD11_48") (pintype "bidirectional"))
    )
    (net (code "81") (name "unconnected-(IC1-PD4{slash}FD12-Pad49)") (class "Default")
      (node (ref "IC1") (pin "49") (pinfunction "PD4/FD12_49") (pintype "bidirectional"))
    )
    (net (code "82") (name "unconnected-(IC1-PD5{slash}FD13-Pad50)") (class "Default")
      (node (ref "IC1") (pin "50") (pinfunction "PD5/FD13_50") (pintype "bidirectional"))
    )
    (net (code "83") (name "unconnected-(IC1-PD6{slash}FD14-Pad51)") (class "Default")
      (node (ref "IC1") (pin "51") (pinfunction "PD6/FD14_51") (pintype "bidirectional"))
    )
    (net (code "84") (name "unconnected-(IC1-RDY0{slash}SLRD-Pad1)") (class "Default")
      (node (ref "IC1") (pin "1") (pinfunction "RDY0/SLRD_1") (pintype "input"))
    )
    (net (code "85") (name "unconnected-(IC1-RDY1{slash}SLRW-Pad2)") (class "Default")
      (node (ref "IC1") (pin "2") (pinfunction "RDY1/SLRW_2") (pintype "input"))
    )
    (net (code "86") (name "unconnected-(U$1A-IND-Pad6)") (class "Default")
      (node (ref "U$1") (pin "6") (pinfunction "IND_6") (pintype "passive"))
    )
    (net (code "87") (name "unconnected-(U$1A-P1_2-Pad13)") (class "Default")
      (node (ref "U$1") (pin "13") (pinfunction "P1_2_13") (pintype "passive"))
    )
    (net (code "88") (name "unconnected-(U$1A-P1_4_TDI-Pad15)") (class "Default")
      (node (ref "U$1") (pin "15") (pinfunction "P1_4_TDI_15") (pintype "passive"))
    )
    (net (code "89") (name "unconnected-(U$1A-P1_5_NTRST-Pad16)") (class "Default")
      (node (ref "U$1") (pin "16") (pinfunction "P1_5_NTRST_16") (pintype "passive"))
    )
    (net (code "90") (name "unconnected-(U$1A-P15_2_KXO-Pad40)") (class "Default")
      (node (ref "U$1") (pin "40") (pinfunction "P15_2_KXO_40") (pintype "passive"))
    )
    (net (code "91") (name "unconnected-(U$1A-P15_3_KXI-Pad41)") (class "Default")
      (node (ref "U$1") (pin "41") (pinfunction "P15_3_KXI_41") (pintype "passive"))
    )
    (net (code "92") (name "unconnected-(U$1A-P15_6_DP-Pad22)") (class "Default")
      (node (ref "U$1") (pin "22") (pinfunction "P15_6_DP_22") (pintype "passive"))
    )
    (net (code "93") (name "unconnected-(U$1A-P15_7_DM-Pad23)") (class "Default")
      (node (ref "U$1") (pin "23") (pinfunction "P15_7_DM_23") (pintype "passive"))
    )
    (net (code "94") (name "unconnected-(U$3-BYPASS-Pad4)") (class "Default")
      (node (ref "U$3") (pin "4") (pinfunction "BYPASS_4") (pintype "bidirectional"))
    )
    (net (code "95") (name "unconnected-(USB-MINIB-MTN1-PadMTN3)") (class "Default")
      (node (ref "USB-MINIB") (pin "MTN3") (pinfunction "MTN1_MTN3") (pintype "bidirectional"))
    )
    (net (code "96") (name "unconnected-(USB-MINIB-MTN2-PadMTN1)") (class "Default")
      (node (ref "USB-MINIB") (pin "MTN1") (pinfunction "MTN2_MTN1") (pintype "bidirectional"))
    )
    (net (code "97") (name "unconnected-(USB-MINIB-MTN3-PadMTN2)") (class "Default")
      (node (ref "USB-MINIB") (pin "MTN2") (pinfunction "MTN3_MTN2") (pintype "bidirectional"))
    )
    (net (code "98") (name "unconnected-(USB-MINIB-PadID)") (class "Default")
      (node (ref "USB-MINIB") (pin "ID") (pinfunction "ID_ID") (pintype "bidirectional"))
    )
  )
)
